# RP2040.net
KiCad netlist of a schematic drawn in Altium Designer
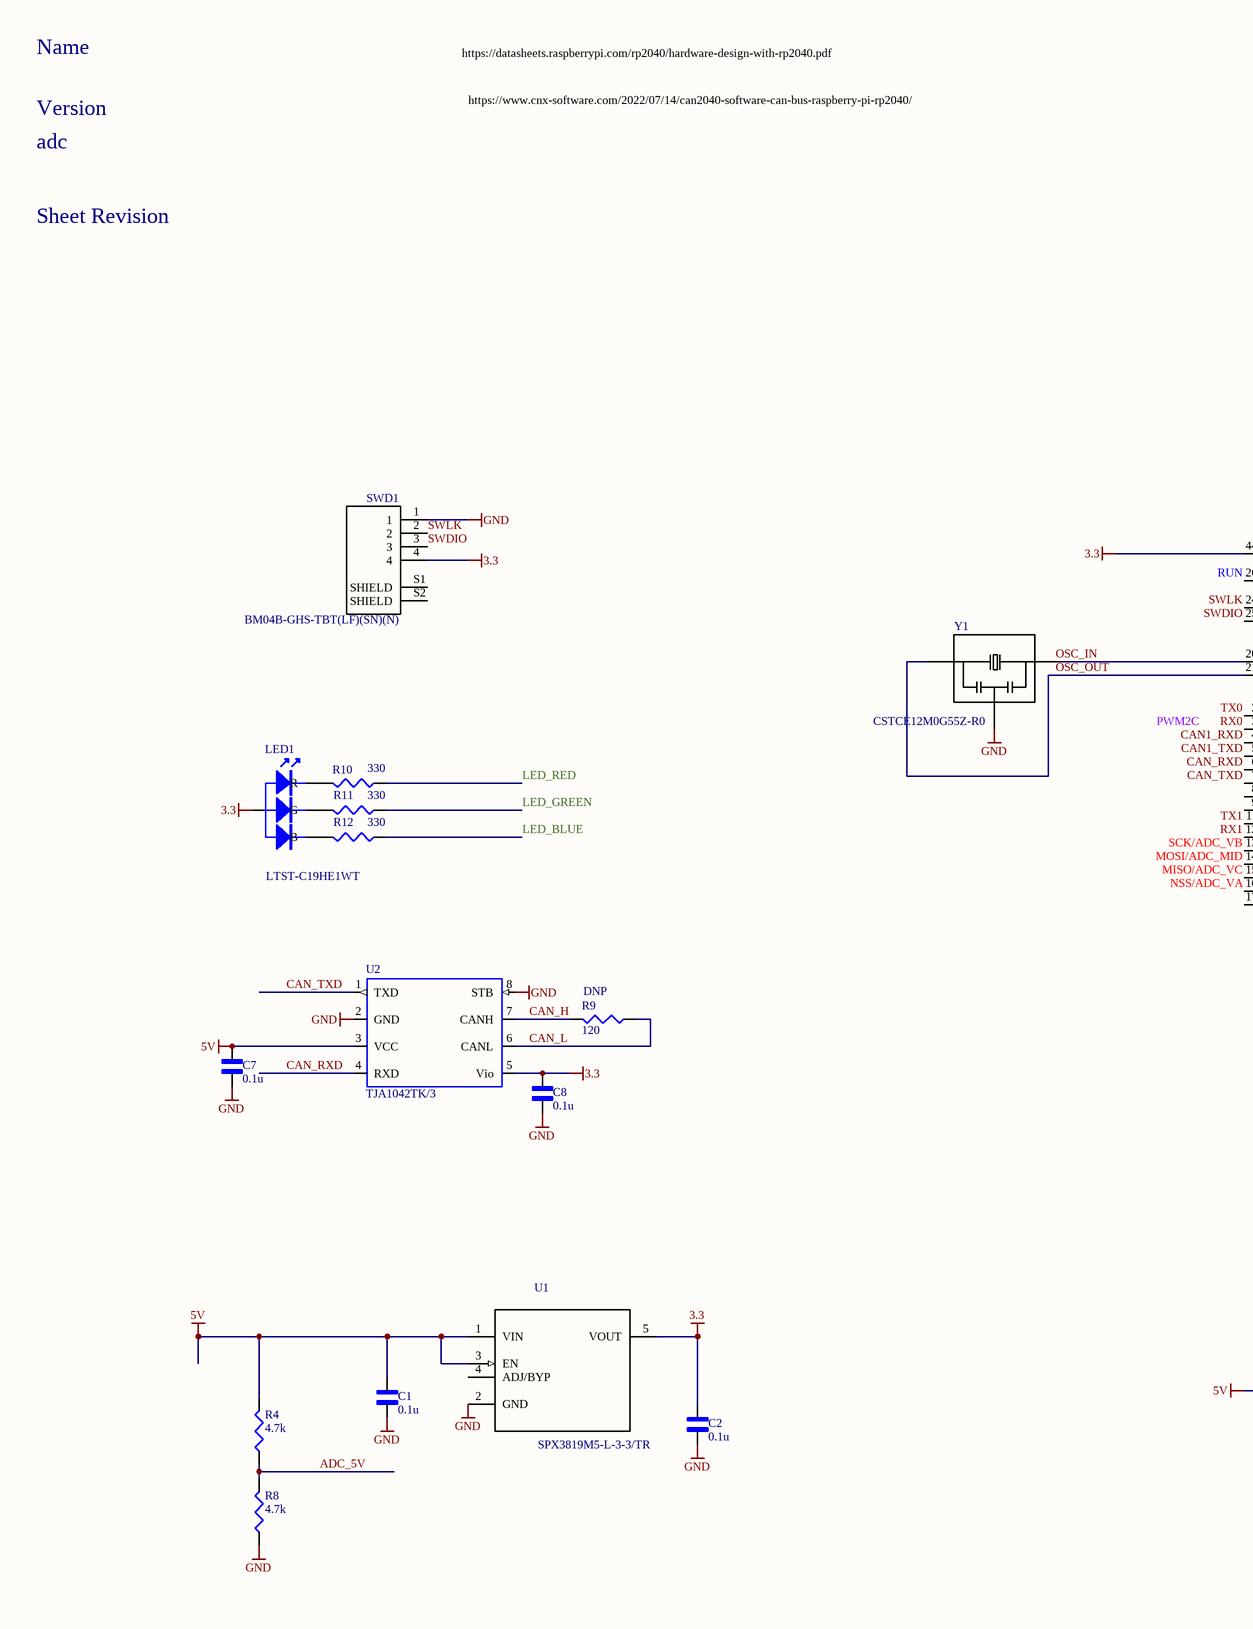
[diagram p0: RP2040.SchDoc, left]
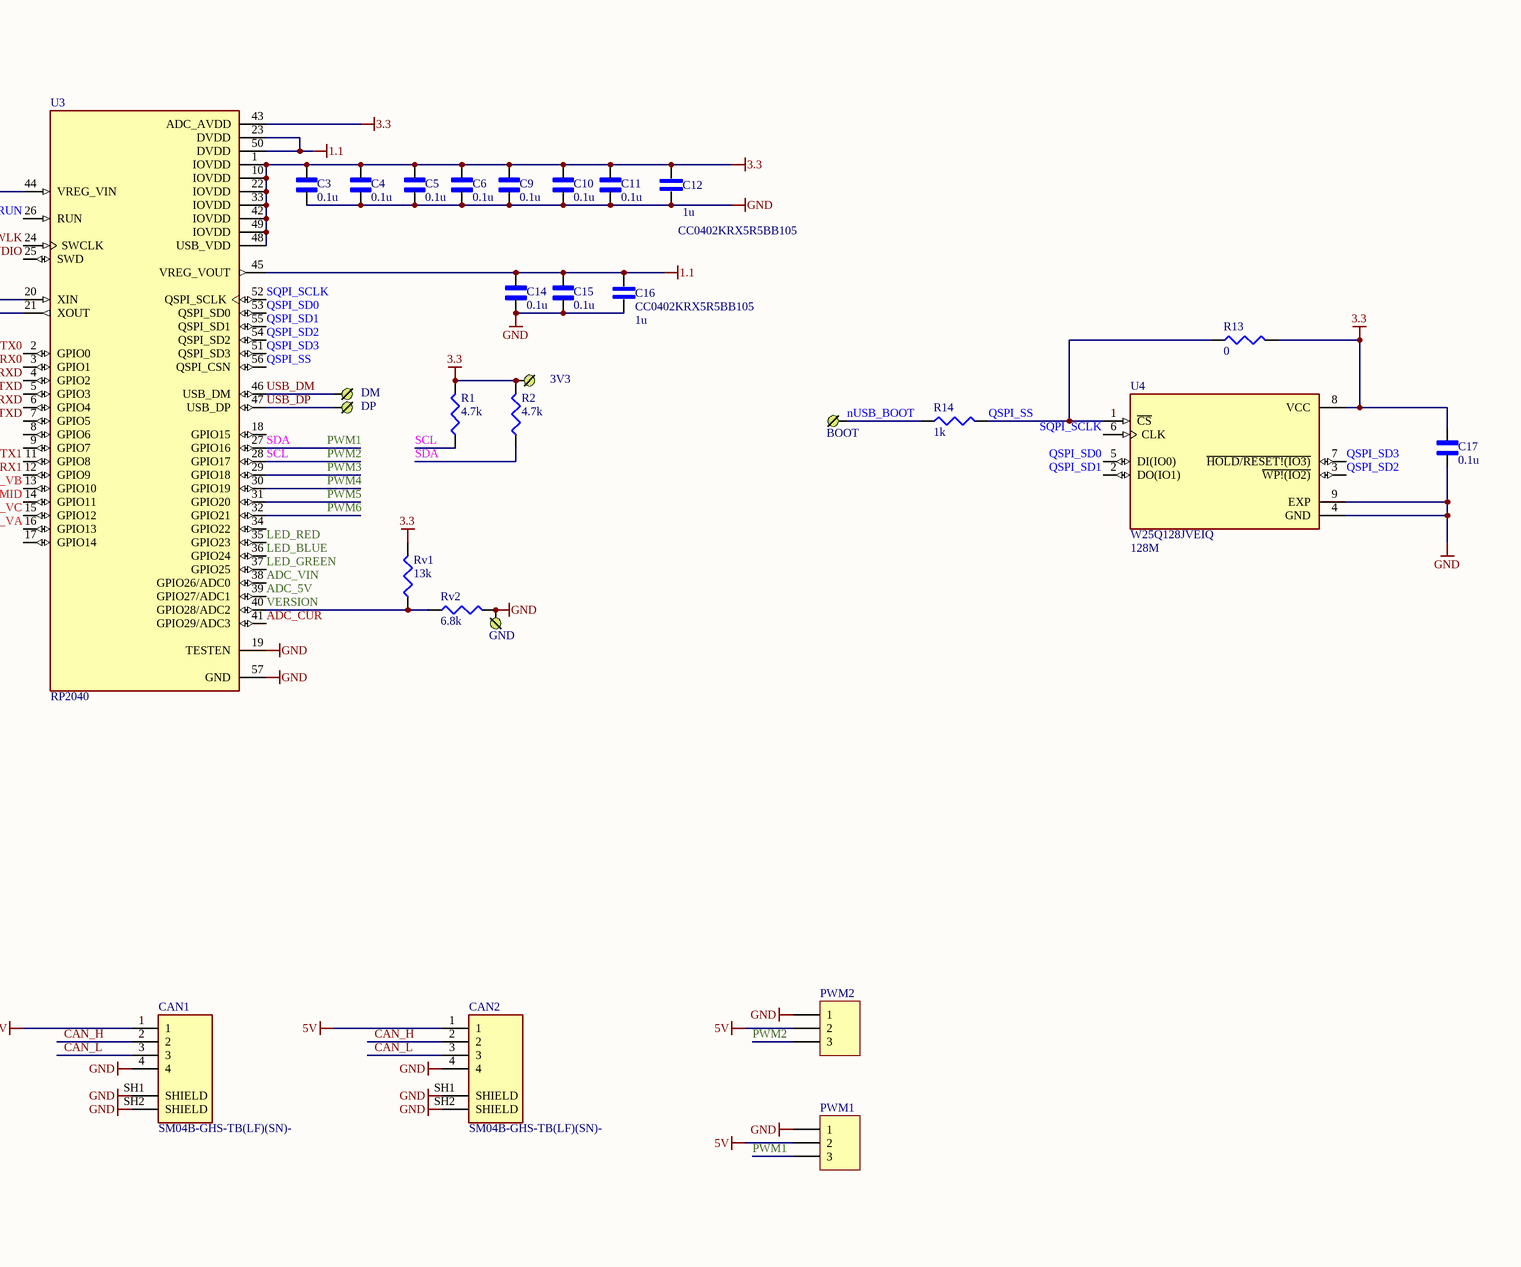
[diagram p1: RP2040.SchDoc, right]

(export (version "E")
  (design (tool "Eeschema 10.0.6"))
  (components
    (comp (ref "3V3") (value "Test Point") (footprint "PAD1") (libsource (lib "lib") (part "PLUG")))
    (comp (ref "BOOT") (value "Test Point") (footprint "PAD1") (libsource (lib "lib") (part "PLUG")))
    (comp (ref "C1")
      (value "0.1u")
      (footprint "CAPC1005X55N")
      (description "GCM155R71H104KE02D, Чип 0402 X7R 0.1uF +10% 50V,Конденсатор")
      (fields (field (name "MF") "Murata") (field (name "MP") "GCM155R71H104KE02D"))
      (libsource (lib "lib") (part "GCM155R71H104KE02D"))
    )
    (comp (ref "C2")
      (value "0.1u")
      (footprint "CAPC1005X55N")
      (description "GCM155R71H104KE02D, Чип 0402 X7R 0.1uF +10% 50V,Конденсатор")
      (fields (field (name "MF") "Murata") (field (name "MP") "GCM155R71H104KE02D"))
      (libsource (lib "lib") (part "GCM155R71H104KE02D"))
    )
    (comp (ref "C3")
      (value "0.1u")
      (footprint "CAPC1005X55N")
      (description "GCM155R71H104KE02D, Чип 0402 X7R 0.1uF +10% 50V,Конденсатор")
      (fields (field (name "MF") "Murata") (field (name "MP") "GCM155R71H104KE02D"))
      (libsource (lib "lib") (part "GCM155R71H104KE02D"))
    )
    (comp (ref "C4")
      (value "0.1u")
      (footprint "CAPC1005X55N")
      (description "GCM155R71H104KE02D, Чип 0402 X7R 0.1uF +10% 50V,Конденсатор")
      (fields (field (name "MF") "Murata") (field (name "MP") "GCM155R71H104KE02D"))
      (libsource (lib "lib") (part "GCM155R71H104KE02D"))
    )
    (comp (ref "C5")
      (value "0.1u")
      (footprint "CAPC1005X55N")
      (description "GCM155R71H104KE02D, Чип 0402 X7R 0.1uF +10% 50V,Конденсатор")
      (fields (field (name "MF") "Murata") (field (name "MP") "GCM155R71H104KE02D"))
      (libsource (lib "lib") (part "GCM155R71H104KE02D"))
    )
    (comp (ref "C6")
      (value "0.1u")
      (footprint "CAPC1005X55N")
      (description "GCM155R71H104KE02D, Чип 0402 X7R 0.1uF +10% 50V,Конденсатор")
      (fields (field (name "MF") "Murata") (field (name "MP") "GCM155R71H104KE02D"))
      (libsource (lib "lib") (part "GCM155R71H104KE02D"))
    )
    (comp (ref "C7")
      (value "0.1u")
      (footprint "CAPC1005X55N")
      (description "GCM155R71H104KE02D, Чип 0402 X7R 0.1uF +10% 50V,Конденсатор")
      (fields (field (name "MF") "Murata") (field (name "MP") "GCM155R71H104KE02D"))
      (libsource (lib "lib") (part "GCM155R71H104KE02D"))
    )
    (comp (ref "C8")
      (value "0.1u")
      (footprint "CAPC1005X55N")
      (description "GCM155R71H104KE02D, Чип 0402 X7R 0.1uF +10% 50V,Конденсатор")
      (fields (field (name "MF") "Murata") (field (name "MP") "GCM155R71H104KE02D"))
      (libsource (lib "lib") (part "GCM155R71H104KE02D"))
    )
    (comp (ref "C9")
      (value "0.1u")
      (footprint "CAPC1005X55N")
      (description "GCM155R71H104KE02D, Чип 0402 X7R 0.1uF +10% 50V,Конденсатор")
      (fields (field (name "MF") "Murata") (field (name "MP") "GCM155R71H104KE02D"))
      (libsource (lib "lib") (part "GCM155R71H104KE02D"))
    )
    (comp (ref "C10")
      (value "0.1u")
      (footprint "CAPC1005X55N")
      (description "GCM155R71H104KE02D, Чип 0402 X7R 0.1uF +10% 50V,Конденсатор")
      (fields (field (name "MF") "Murata") (field (name "MP") "GCM155R71H104KE02D"))
      (libsource (lib "lib") (part "GCM155R71H104KE02D"))
    )
    (comp (ref "C11")
      (value "0.1u")
      (footprint "CAPC1005X55N")
      (description "GCM155R71H104KE02D, Чип 0402 X7R 0.1uF +10% 50V,Конденсатор")
      (fields (field (name "MF") "Murata") (field (name "MP") "GCM155R71H104KE02D"))
      (libsource (lib "lib") (part "GCM155R71H104KE02D"))
    )
    (comp (ref "C12")
      (value "CC0402KRX5R5BB105")
      (footprint "CAPC1005X55N")
      (description "10% 6.3V Ceramic Capacitor X5R 0402 _1005 Metric_")
      (fields (field (name "MF") "Yageo") (field (name "ALTIUM_VALUE") "1u"))
      (libsource (lib "lib") (part "CC0402KRX5R5BB105"))
    )
    (comp (ref "C14")
      (value "0.1u")
      (footprint "CAPC1005X55N")
      (description "GCM155R71H104KE02D, Чип 0402 X7R 0.1uF +10% 50V,Конденсатор")
      (fields (field (name "MF") "Murata") (field (name "MP") "GCM155R71H104KE02D"))
      (libsource (lib "lib") (part "GCM155R71H104KE02D"))
    )
    (comp (ref "C15")
      (value "0.1u")
      (footprint "CAPC1005X55N")
      (description "GCM155R71H104KE02D, Чип 0402 X7R 0.1uF +10% 50V,Конденсатор")
      (fields (field (name "MF") "Murata") (field (name "MP") "GCM155R71H104KE02D"))
      (libsource (lib "lib") (part "GCM155R71H104KE02D"))
    )
    (comp (ref "C16")
      (value "CC0402KRX5R5BB105")
      (footprint "CAPC1005X55N")
      (description "10% 6.3V Ceramic Capacitor X5R 0402 _1005 Metric_")
      (fields (field (name "MF") "Yageo") (field (name "ALTIUM_VALUE") "1u"))
      (libsource (lib "lib") (part "CC0402KRX5R5BB105"))
    )
    (comp (ref "C17")
      (value "0.1u")
      (footprint "CAPC1005X55N")
      (description "GCM155R71H104KE02D, Чип 0402 X7R 0.1uF +10% 50V,Конденсатор")
      (fields (field (name "MF") "Murata") (field (name "MP") "GCM155R71H104KE02D"))
      (libsource (lib "lib") (part "GCM155R71H104KE02D"))
    )
    (comp (ref "CAN1")
      (value "SM04B-GHS-TB(LF)(SN)-")
      (footprint "JST_SM04B-GHS-TB(LF)(SN)-")
      (description "Connector Header Surface Mount, Right Angle 4 position 0.049 _1.25mm_")
      (fields (field (name "MP") "SM04B-GHS-TB(LF)(SN)") (field (name "MF") "JST Sales"))
      (libsource (lib "lib") (part "SM04B-GHS-TB(LF)(SN)-"))
    )
    (comp (ref "CAN2")
      (value "SM04B-GHS-TB(LF)(SN)-")
      (footprint "JST_SM04B-GHS-TB(LF)(SN)-")
      (description "Connector Header Surface Mount, Right Angle 4 position 0.049 _1.25mm_")
      (fields (field (name "MP") "SM04B-GHS-TB(LF)(SN)") (field (name "MF") "JST Sales"))
      (libsource (lib "lib") (part "SM04B-GHS-TB(LF)(SN)-"))
    )
    (comp (ref "DM") (value "Test Point") (footprint "PAD1") (libsource (lib "lib") (part "PLUG")))
    (comp (ref "DP") (value "Test Point") (footprint "PAD1") (libsource (lib "lib") (part "PLUG")))
    (comp (ref "GND") (value "Test Point") (footprint "PAD1") (libsource (lib "lib") (part "PLUG")))
    (comp (ref "LED1")
      (value "LTST-C19HE1WT")
      (footprint "LTST-C19HE1WT")
      (description "Blue/Green/Red")
      (libsource (lib "lib") (part "RGB_LED_5MM"))
    )
    (comp (ref "PWM1")
      (value "A")
      (footprint "HDR Side 3 pin")
      (description "Header, 3-Pin")
      (fields (field (name "MF") "Connfly electronic (Zhenqin)") (field (name "MP") "PLS-3 (DS1021-1x3)"))
      (libsource (lib "DC_DC") (part "Header 3"))
    )
    (comp (ref "PWM2")
      (value "A")
      (footprint "HDR Side 3 pin")
      (description "Header, 3-Pin")
      (fields (field (name "MF") "Connfly electronic (Zhenqin)") (field (name "MP") "PLS-3 (DS1021-1x3)"))
      (libsource (lib "DC_DC") (part "Header 3"))
    )
    (comp (ref "R1")
      (value "4.7k")
      (footprint "RESC1005X40N")
      (description "0.062Вт 0402 4.7 кОм, 1%, Чип резистор (SMD)")
      (fields (field (name "MF") "Yageo or NXP") (field (name "MP") "RC0402FR-074K7L"))
      (libsource (lib "lib") (part "RC0402FR-074K7L"))
    )
    (comp (ref "R2")
      (value "4.7k")
      (footprint "RESC1005X40N")
      (description "0.062Вт 0402 4.7 кОм, 1%, Чип резистор (SMD)")
      (fields (field (name "MF") "Yageo or NXP") (field (name "MP") "RC0402FR-074K7L"))
      (libsource (lib "lib") (part "RC0402FR-074K7L"))
    )
    (comp (ref "R4")
      (value "4.7k")
      (footprint "RESC1005X40N")
      (description "0.062Вт 0402 4.7 кОм, 1%, Чип резистор (SMD)")
      (fields (field (name "MF") "Yageo or NXP") (field (name "MP") "RC0402FR-074K7L"))
      (libsource (lib "lib") (part "RC0402FR-074K7L"))
    )
    (comp (ref "R8")
      (value "4.7k")
      (footprint "RESC1005X40N")
      (description "0.062Вт 0402 4.7 кОм, 1%, Чип резистор (SMD)")
      (fields (field (name "MF") "Yageo or NXP") (field (name "MP") "RC0402FR-074K7L"))
      (libsource (lib "lib") (part "RC0402FR-074K7L"))
    )
    (comp (ref "R9")
      (value "120")
      (footprint "J1-0603")
      (description "120 Ohms 1 0.1 W 1 10 W Chip Resistor 0603 1608 Metric Thick Film")
      (fields
        (field (name "INSTRUCTIONS") "DNP")
        (field (name "MP") "RC0603FR-07120RL")
        (field (name "Comment") "Res3")
      )
      (libsource (lib "Miscellaneous Devices") (part "Res3"))
    )
    (comp (ref "R10")
      (value "330")
      (footprint "RESC1005X40N")
      (description "0.062Вт 0402 330 Ом, 1%, Чип резистор (SMD)")
      (fields (field (name "MF") "Yageo or NXP") (field (name "MP") "RC0402FR-07330RL"))
      (libsource (lib "lib") (part "RC0402FR-07330RL"))
    )
    (comp (ref "R11")
      (value "330")
      (footprint "RESC1005X40N")
      (description "0.062Вт 0402 330 Ом, 1%, Чип резистор (SMD)")
      (fields (field (name "MF") "Yageo or NXP") (field (name "MP") "RC0402FR-07330RL"))
      (libsource (lib "lib") (part "RC0402FR-07330RL"))
    )
    (comp (ref "R12")
      (value "330")
      (footprint "RESC1005X40N")
      (description "0.062Вт 0402 330 Ом, 1%, Чип резистор (SMD)")
      (fields (field (name "MF") "Yageo or NXP") (field (name "MP") "RC0402FR-07330RL"))
      (libsource (lib "lib") (part "RC0402FR-07330RL"))
    )
    (comp (ref "R13")
      (value "0")
      (footprint "J1-0603")
      (description "0 Ohms ±1% 0.1W, 1/10W Chip Resistor 0603 (1608 Metric) Moisture Resistant Thick Film")
      (fields (field (name "MF") "Yageo or NXP") (field (name "MP") "RC0603FR-070RL"))
      (libsource (lib "lib") (part "RC0603FR-070RL"))
    )
    (comp (ref "R14")
      (value "1k")
      (footprint "RESC1005X40N")
      (description "0.062Вт 0402 1 кОм, 1%, Чип резистор (SMD)")
      (fields (field (name "MF") "Yageo or NXP") (field (name "MP") "RC0402FR-071KL"))
      (libsource (lib "lib") (part "RC0402FR-071KL"))
    )
    (comp (ref "Rv1")
      (value "13k")
      (footprint "RESC1005X40N")
      (description "0.062Вт 0402 13 кОм, 1%, Чип резистор (SMD)")
      (fields (field (name "MF") "Yageo or NXP") (field (name "MP") "RC0402FR-0713KL"))
      (libsource (lib "lib") (part "RC0402FR-0713KL"))
    )
    (comp (ref "Rv2")
      (value "6.8k")
      (footprint "RESC1005X40N")
      (description "0.062Вт 0402 6.8 кОм, 1%, Чип резистор (SMD)")
      (fields (field (name "MF") "Yageo or NXP") (field (name "MP") "RC0402FR-076K8L"))
      (libsource (lib "lib") (part "RC0402FR-076K8L"))
    )
    (comp (ref "SWD1")
      (value "BM04B-GHS-TBT(LF)(SN)(N)")
      (footprint "JST_BM04B-GHS-holes")
      (description "Conn Shrouded Header HDR 4 POS 1.25mm Solder ST SMD Reel")
      (fields (field (name "MF") "JST Sales") (field (name "MP") "SM04B-GHS-TB(LF)(SN)"))
      (libsource (lib "lib") (part "BM04B-GHS-TBT(LF)(SN)(N)"))
    )
    (comp (ref "U1")
      (value "SPX3819M5-L-3-3/TR")
      (footprint "*SOT95P280X145-5N")
      (description "Low Dropout Voltage Regulator, Adjustable 0.5A, В±1%, 2.5 to 16 Vin, 5-Pin SOT-23")
      (fields (field (name "MF") "MaxLinear, Inc."))
      (libsource (lib "DC_DC") (part "SPX3819M5-L"))
    )
    (comp (ref "U2")
      (value "TJA1042TK/3")
      (footprint "SOT782-1")
      (description "1/1 Transceiver Half CANbus 8-SO")
      (fields (field (name "MF") "NXP USA"))
      (libsource (lib "lib") (part "TJA1042TK/3"))
    )
    (comp (ref "U3")
      (value "RP2040")
      (footprint "QFN40P700X700X90-57N")
      (libsource (lib "lib") (part "RP2040"))
    )
    (comp (ref "U4")
      (value "W25Q128JVEIQ")
      (footprint "SON127P500X600X80-9N")
      (description "FLASH - NOR Memory IC 128Mb (16M x 8) SPI - Quad I/O, QPI, DTR 133 MHz 8-SOIC")
      (fields
        (field (name "MF") "Winbond Electronics")
        (field (name "MP") "W25Q128JVSIQ")
        (field (name "ALTIUM_VALUE") "128M")
      )
      (libsource (lib "lib") (part "W25Q128JVEIQ"))
    )
    (comp (ref "Y1")
      (value "CSTCE12M0G55Z-R0")
      (footprint "*OSC_CSTCE8M00G55-R0")
      (description "Ceramic Resonator, 12 MHz, +/- 0.5%, -40 to 125 degC, 3-Pin SMD, RoHS, Tape and Reel")
      (fields (field (name "MF") "Murata"))
      (libsource (lib "lib") (part "CSTCE12M0G55Z-R0"))
    )
  )
  (nets
    (net (code "1") (name "/ADC_5V") (class "Default")
      (node (ref "R4") (pin "1") (pinfunction "1_1") (pintype "passive"))
      (node (ref "R8") (pin "2") (pinfunction "2_2") (pintype "passive"))
      (node (ref "U3") (pin "39") (pinfunction "GPIO27/ADC1_39") (pintype "bidirectional"))
    )
    (net (code "2") (name "/ADC_CUR") (class "Default")
      (node (ref "U3") (pin "41") (pinfunction "GPIO29/ADC3_41") (pintype "bidirectional"))
    )
    (net (code "3") (name "/ADC_VIN") (class "Default")
      (node (ref "U3") (pin "38") (pinfunction "GPIO26/ADC0_38") (pintype "bidirectional"))
    )
    (net (code "4") (name "/CAN1_RXD") (class "Default")
      (node (ref "U3") (pin "4") (pinfunction "GPIO2_4") (pintype "bidirectional"))
    )
    (net (code "5") (name "/CAN1_TXD") (class "Default")
      (node (ref "U3") (pin "5") (pinfunction "GPIO3_5") (pintype "bidirectional"))
    )
    (net (code "6") (name "/CAN_H") (class "Default")
      (node (ref "CAN1") (pin "2") (pinfunction "2_2") (pintype "passive"))
      (node (ref "CAN2") (pin "2") (pinfunction "2_2") (pintype "passive"))
      (node (ref "R9") (pin "2") (pinfunction "2_2") (pintype "passive"))
      (node (ref "U2") (pin "7") (pinfunction "CANH_7") (pintype "bidirectional"))
    )
    (net (code "7") (name "/CAN_L") (class "Default")
      (node (ref "CAN1") (pin "3") (pinfunction "3_3") (pintype "passive"))
      (node (ref "CAN2") (pin "3") (pinfunction "3_3") (pintype "passive"))
      (node (ref "R9") (pin "1") (pinfunction "1_1") (pintype "passive"))
      (node (ref "U2") (pin "6") (pinfunction "CANL_6") (pintype "bidirectional"))
    )
    (net (code "8") (name "/CAN_RXD") (class "Default")
      (node (ref "U2") (pin "4") (pinfunction "RXD_4") (pintype "bidirectional"))
      (node (ref "U3") (pin "6") (pinfunction "GPIO4_6") (pintype "bidirectional"))
    )
    (net (code "9") (name "/CAN_TXD") (class "Default")
      (node (ref "U2") (pin "1") (pinfunction "TXD_1") (pintype "output"))
      (node (ref "U3") (pin "7") (pinfunction "GPIO5_7") (pintype "bidirectional"))
    )
    (net (code "10") (name "/LED_BLUE") (class "Default")
      (node (ref "R12") (pin "1") (pinfunction "1_1") (pintype "passive"))
      (node (ref "U3") (pin "36") (pinfunction "GPIO24_36") (pintype "bidirectional"))
    )
    (net (code "11") (name "/LED_GREEN") (class "Default")
      (node (ref "R11") (pin "1") (pinfunction "1_1") (pintype "passive"))
      (node (ref "U3") (pin "37") (pinfunction "GPIO25_37") (pintype "bidirectional"))
    )
    (net (code "12") (name "/LED_RED") (class "Default")
      (node (ref "R10") (pin "1") (pinfunction "1_1") (pintype "passive"))
      (node (ref "U3") (pin "35") (pinfunction "GPIO23_35") (pintype "bidirectional"))
    )
    (net (code "13") (name "/MISO{slash}ADC_VC") (class "Default")
      (node (ref "U3") (pin "15") (pinfunction "GPIO12_15") (pintype "bidirectional"))
    )
    (net (code "14") (name "/MOSI{slash}ADC_MID") (class "Default")
      (node (ref "U3") (pin "14") (pinfunction "GPIO11_14") (pintype "bidirectional"))
    )
    (net (code "15") (name "/NSS{slash}ADC_VA") (class "Default")
      (node (ref "U3") (pin "16") (pinfunction "GPIO13_16") (pintype "bidirectional"))
    )
    (net (code "17") (name "/OSC_OUT") (class "Default")
      (node (ref "U3") (pin "21") (pinfunction "XOUT_21") (pintype "output"))
      (node (ref "Y1") (pin "1") (pinfunction "1_1") (pintype "passive"))
    )
    (net (code "18") (name "/PWM1") (class "Default")
      (node (ref "PWM1") (pin "3") (pinfunction "3_3") (pintype "passive"))
      (node (ref "R2") (pin "1") (pinfunction "1_1") (pintype "passive"))
      (node (ref "U3") (pin "27") (pinfunction "GPIO16_27") (pintype "bidirectional"))
    )
    (net (code "19") (name "/PWM2") (class "Default")
      (node (ref "PWM2") (pin "3") (pinfunction "3_3") (pintype "passive"))
      (node (ref "R1") (pin "1") (pinfunction "1_1") (pintype "passive"))
      (node (ref "U3") (pin "28") (pinfunction "GPIO17_28") (pintype "bidirectional"))
    )
    (net (code "21") (name "/PWM3") (class "Default")
      (node (ref "U3") (pin "29") (pinfunction "GPIO18_29") (pintype "bidirectional"))
    )
    (net (code "22") (name "/PWM4") (class "Default")
      (node (ref "U3") (pin "30") (pinfunction "GPIO19_30") (pintype "bidirectional"))
    )
    (net (code "23") (name "/PWM5") (class "Default")
      (node (ref "U3") (pin "31") (pinfunction "GPIO20_31") (pintype "bidirectional"))
    )
    (net (code "24") (name "/PWM6") (class "Default")
      (node (ref "U3") (pin "32") (pinfunction "GPIO21_32") (pintype "bidirectional"))
    )
    (net (code "25") (name "/QSPI_SD0") (class "Default")
      (node (ref "U3") (pin "53") (pinfunction "QSPI_SD0_53") (pintype "bidirectional"))
      (node (ref "U4") (pin "5") (pinfunction "DI(IO0)_5") (pintype "bidirectional"))
    )
    (net (code "26") (name "/QSPI_SD1") (class "Default")
      (node (ref "U3") (pin "55") (pinfunction "QSPI_SD1_55") (pintype "bidirectional"))
      (node (ref "U4") (pin "2") (pinfunction "DO(IO1)_2") (pintype "bidirectional"))
    )
    (net (code "27") (name "/QSPI_SD2") (class "Default")
      (node (ref "U3") (pin "54") (pinfunction "QSPI_SD2_54") (pintype "bidirectional"))
      (node (ref "U4") (pin "3") (pinfunction "~{WP!(IO2)}_3") (pintype "bidirectional"))
    )
    (net (code "28") (name "/QSPI_SD3") (class "Default")
      (node (ref "U3") (pin "51") (pinfunction "QSPI_SD3_51") (pintype "bidirectional"))
      (node (ref "U4") (pin "7") (pinfunction "~{HOLD/RESET!(IO3)}_7") (pintype "bidirectional"))
    )
    (net (code "29") (name "/QSPI_SS") (class "Default")
      (node (ref "R13") (pin "1") (pinfunction "1_1") (pintype "passive"))
      (node (ref "R14") (pin "2") (pinfunction "2_2") (pintype "passive"))
      (node (ref "U3") (pin "56") (pinfunction "QSPI_CSN_56") (pintype "bidirectional"))
      (node (ref "U4") (pin "1") (pinfunction "~{CS}_1") (pintype "input"))
    )
    (net (code "30") (name "/RUN") (class "Default")
      (node (ref "U3") (pin "26") (pinfunction "RUN_26") (pintype "input"))
    )
    (net (code "31") (name "/RX0") (class "Default")
      (node (ref "U3") (pin "3") (pinfunction "GPIO1_3") (pintype "bidirectional"))
    )
    (net (code "32") (name "/RX1") (class "Default")
      (node (ref "U3") (pin "12") (pinfunction "GPIO9_12") (pintype "bidirectional"))
    )
    (net (code "33") (name "/SCK{slash}ADC_VB") (class "Default")
      (node (ref "U3") (pin "13") (pinfunction "GPIO10_13") (pintype "bidirectional"))
    )
    (net (code "34") (name "/SQPI_SCLK") (class "Default")
      (node (ref "U3") (pin "52") (pinfunction "QSPI_SCLK_52") (pintype "bidirectional"))
      (node (ref "U4") (pin "6") (pinfunction "CLK_6") (pintype "input"))
    )
    (net (code "35") (name "/SWDIO") (class "Default")
      (node (ref "SWD1") (pin "3") (pinfunction "3_3") (pintype "passive"))
      (node (ref "U3") (pin "25") (pinfunction "SWD_25") (pintype "bidirectional"))
    )
    (net (code "36") (name "/SWLK") (class "Default")
      (node (ref "SWD1") (pin "2") (pinfunction "2_2") (pintype "passive"))
      (node (ref "U3") (pin "24") (pinfunction "SWCLK_24") (pintype "input"))
    )
    (net (code "37") (name "/TX0") (class "Default")
      (node (ref "U3") (pin "2") (pinfunction "GPIO0_2") (pintype "bidirectional"))
    )
    (net (code "38") (name "/TX1") (class "Default")
      (node (ref "U3") (pin "11") (pinfunction "GPIO8_11") (pintype "bidirectional"))
    )
    (net (code "39") (name "/USB_DM") (class "Default")
      (node (ref "DM") (pin "1") (pintype "passive"))
      (node (ref "U3") (pin "46") (pinfunction "USB_DM_46") (pintype "bidirectional"))
    )
    (net (code "40") (name "/USB_DP") (class "Default")
      (node (ref "DP") (pin "1") (pintype "passive"))
      (node (ref "U3") (pin "47") (pinfunction "USB_DP_47") (pintype "bidirectional"))
    )
    (net (code "41") (name "/VERSION") (class "Default")
      (node (ref "Rv1") (pin "1") (pinfunction "1_1") (pintype "passive"))
      (node (ref "Rv2") (pin "1") (pinfunction "1_1") (pintype "passive"))
      (node (ref "U3") (pin "40") (pinfunction "GPIO28/ADC2_40") (pintype "bidirectional"))
    )
    (net (code "42") (name "/nUSB_BOOT") (class "Default")
      (node (ref "BOOT") (pin "1") (pintype "passive"))
      (node (ref "R14") (pin "1") (pinfunction "1_1") (pintype "passive"))
    )
    (net (code "43") (name "1.1") (class "Default")
      (node (ref "C14") (pin "2") (pinfunction "2_2") (pintype "passive"))
      (node (ref "C15") (pin "2") (pinfunction "2_2") (pintype "passive"))
      (node (ref "C16") (pin "1") (pinfunction "1_1") (pintype "passive"))
      (node (ref "U3") (pin "23") (pinfunction "DVDD_23") (pintype "power_in"))
      (node (ref "U3") (pin "45") (pinfunction "VREG_VOUT_45") (pintype "output"))
      (node (ref "U3") (pin "50") (pinfunction "DVDD_50") (pintype "power_in"))
    )
    (net (code "44") (name "3.3") (class "Default")
      (node (ref "3V3") (pin "1") (pintype "passive"))
      (node (ref "C10") (pin "2") (pinfunction "2_2") (pintype "passive"))
      (node (ref "C11") (pin "2") (pinfunction "2_2") (pintype "passive"))
      (node (ref "C12") (pin "1") (pinfunction "1_1") (pintype "passive"))
      (node (ref "C17") (pin "2") (pinfunction "2_2") (pintype "passive"))
      (node (ref "C2") (pin "2") (pinfunction "2_2") (pintype "passive"))
      (node (ref "C3") (pin "2") (pinfunction "2_2") (pintype "passive"))
      (node (ref "C4") (pin "2") (pinfunction "2_2") (pintype "passive"))
      (node (ref "C5") (pin "2") (pinfunction "2_2") (pintype "passive"))
      (node (ref "C6") (pin "2") (pinfunction "2_2") (pintype "passive"))
      (node (ref "C8") (pin "2") (pinfunction "2_2") (pintype "passive"))
      (node (ref "C9") (pin "2") (pinfunction "2_2") (pintype "passive"))
      (node (ref "LED1") (pin "4") (pinfunction "A_4") (pintype "passive"))
      (node (ref "R1") (pin "2") (pinfunction "2_2") (pintype "passive"))
      (node (ref "R13") (pin "2") (pinfunction "2_2") (pintype "passive"))
      (node (ref "R2") (pin "2") (pinfunction "2_2") (pintype "passive"))
      (node (ref "Rv1") (pin "2") (pinfunction "2_2") (pintype "passive"))
      (node (ref "SWD1") (pin "4") (pinfunction "4_4") (pintype "passive"))
      (node (ref "U1") (pin "5") (pinfunction "VOUT_5") (pintype "power_in"))
      (node (ref "U2") (pin "5") (pinfunction "Vio_5") (pintype "power_in"))
      (node (ref "U3") (pin "1") (pinfunction "IOVDD_1") (pintype "power_in"))
      (node (ref "U3") (pin "10") (pinfunction "IOVDD_10") (pintype "power_in"))
      (node (ref "U3") (pin "22") (pinfunction "IOVDD_22") (pintype "power_in"))
      (node (ref "U3") (pin "33") (pinfunction "IOVDD_33") (pintype "power_in"))
      (node (ref "U3") (pin "42") (pinfunction "IOVDD_42") (pintype "power_in"))
      (node (ref "U3") (pin "43") (pinfunction "ADC_AVDD_43") (pintype "power_in"))
      (node (ref "U3") (pin "44") (pinfunction "VREG_VIN_44") (pintype "input"))
      (node (ref "U3") (pin "48") (pinfunction "USB_VDD_48") (pintype "power_in"))
      (node (ref "U3") (pin "49") (pinfunction "IOVDD_49") (pintype "power_in"))
      (node (ref "U4") (pin "8") (pinfunction "VCC_8") (pintype "power_in"))
    )
    (net (code "45") (name "5V") (class "Default")
      (node (ref "C1") (pin "2") (pinfunction "2_2") (pintype "passive"))
      (node (ref "C7") (pin "2") (pinfunction "2_2") (pintype "passive"))
      (node (ref "CAN1") (pin "1") (pinfunction "1_1") (pintype "passive"))
      (node (ref "CAN2") (pin "1") (pinfunction "1_1") (pintype "passive"))
      (node (ref "PWM1") (pin "2") (pinfunction "2_2") (pintype "passive"))
      (node (ref "PWM2") (pin "2") (pinfunction "2_2") (pintype "passive"))
      (node (ref "R4") (pin "2") (pinfunction "2_2") (pintype "passive"))
      (node (ref "U1") (pin "1") (pinfunction "VIN_1") (pintype "power_in"))
      (node (ref "U1") (pin "3") (pinfunction "EN_3") (pintype "input"))
      (node (ref "U2") (pin "3") (pinfunction "VCC_3") (pintype "power_in"))
    )
    (net (code "46") (name "GND") (class "Default")
      (node (ref "C1") (pin "1") (pinfunction "1_1") (pintype "passive"))
      (node (ref "C10") (pin "1") (pinfunction "1_1") (pintype "passive"))
      (node (ref "C11") (pin "1") (pinfunction "1_1") (pintype "passive"))
      (node (ref "C12") (pin "2") (pinfunction "2_2") (pintype "passive"))
      (node (ref "C14") (pin "1") (pinfunction "1_1") (pintype "passive"))
      (node (ref "C15") (pin "1") (pinfunction "1_1") (pintype "passive"))
      (node (ref "C16") (pin "2") (pinfunction "2_2") (pintype "passive"))
      (node (ref "C17") (pin "1") (pinfunction "1_1") (pintype "passive"))
      (node (ref "C2") (pin "1") (pinfunction "1_1") (pintype "passive"))
      (node (ref "C3") (pin "1") (pinfunction "1_1") (pintype "passive"))
      (node (ref "C4") (pin "1") (pinfunction "1_1") (pintype "passive"))
      (node (ref "C5") (pin "1") (pinfunction "1_1") (pintype "passive"))
      (node (ref "C6") (pin "1") (pinfunction "1_1") (pintype "passive"))
      (node (ref "C7") (pin "1") (pinfunction "1_1") (pintype "passive"))
      (node (ref "C8") (pin "1") (pinfunction "1_1") (pintype "passive"))
      (node (ref "C9") (pin "1") (pinfunction "1_1") (pintype "passive"))
      (node (ref "CAN1") (pin "4") (pinfunction "4_4") (pintype "passive"))
      (node (ref "CAN1") (pin "SH1") (pinfunction "SHIELD_SH1") (pintype "power_in"))
      (node (ref "CAN1") (pin "SH2") (pinfunction "SHIELD_SH2") (pintype "power_in"))
      (node (ref "CAN2") (pin "4") (pinfunction "4_4") (pintype "passive"))
      (node (ref "CAN2") (pin "SH1") (pinfunction "SHIELD_SH1") (pintype "power_in"))
      (node (ref "CAN2") (pin "SH2") (pinfunction "SHIELD_SH2") (pintype "power_in"))
      (node (ref "GND") (pin "1") (pintype "passive"))
      (node (ref "PWM1") (pin "1") (pinfunction "1_1") (pintype "passive"))
      (node (ref "PWM2") (pin "1") (pinfunction "1_1") (pintype "passive"))
      (node (ref "R8") (pin "1") (pinfunction "1_1") (pintype "passive"))
      (node (ref "Rv2") (pin "2") (pinfunction "2_2") (pintype "passive"))
      (node (ref "SWD1") (pin "1") (pinfunction "1_1") (pintype "passive"))
      (node (ref "U1") (pin "2") (pinfunction "GND_2") (pintype "passive"))
      (node (ref "U2") (pin "2") (pinfunction "GND_2") (pintype "power_in"))
      (node (ref "U2") (pin "8") (pinfunction "STB_8") (pintype "input"))
      (node (ref "U3") (pin "19") (pinfunction "TESTEN_19") (pintype "passive"))
      (node (ref "U3") (pin "57") (pinfunction "GND_57") (pintype "power_in"))
      (node (ref "U4") (pin "4") (pinfunction "GND_4") (pintype "power_in"))
      (node (ref "U4") (pin "9") (pinfunction "EXP_9") (pintype "passive"))
      (node (ref "Y1") (pin "2") (pinfunction "2_2") (pintype "power_in"))
    )
    (net (code "47") (name "Net-(LED1-B)") (class "Default")
      (node (ref "LED1") (pin "3") (pinfunction "B_3") (pintype "passive"))
      (node (ref "R12") (pin "2") (pinfunction "2_2") (pintype "passive"))
    )
    (net (code "48") (name "Net-(LED1-G)") (class "Default")
      (node (ref "LED1") (pin "2") (pinfunction "G_2") (pintype "passive"))
      (node (ref "R11") (pin "2") (pinfunction "2_2") (pintype "passive"))
    )
    (net (code "49") (name "Net-(LED1-R)") (class "Default")
      (node (ref "LED1") (pin "1") (pinfunction "R_1") (pintype "passive"))
      (node (ref "R10") (pin "2") (pinfunction "2_2") (pintype "passive"))
    )
    (net (code "50") (name "Net-(U3-XIN)") (class "Default")
      (node (ref "U3") (pin "20") (pinfunction "XIN_20") (pintype "input"))
      (node (ref "Y1") (pin "3") (pinfunction "3_3") (pintype "passive"))
    )
    (net (code "51") (name "unconnected-(SWD1-SHIELD-PadS1)") (class "Default")
      (node (ref "SWD1") (pin "S1") (pinfunction "SHIELD_S1") (pintype "passive"))
    )
    (net (code "52") (name "unconnected-(SWD1-SHIELD-PadS2)") (class "Default")
      (node (ref "SWD1") (pin "S2") (pinfunction "SHIELD_S2") (pintype "passive"))
    )
    (net (code "53") (name "unconnected-(U1-ADJ{slash}BYP-Pad4)") (class "Default")
      (node (ref "U1") (pin "4") (pinfunction "ADJ/BYP_4") (pintype "passive"))
    )
    (net (code "54") (name "unconnected-(U3-GPIO6-Pad8)") (class "Default")
      (node (ref "U3") (pin "8") (pinfunction "GPIO6_8") (pintype "bidirectional"))
    )
    (net (code "55") (name "unconnected-(U3-GPIO7-Pad9)") (class "Default")
      (node (ref "U3") (pin "9") (pinfunction "GPIO7_9") (pintype "bidirectional"))
    )
    (net (code "56") (name "unconnected-(U3-GPIO14-Pad17)") (class "Default")
      (node (ref "U3") (pin "17") (pinfunction "GPIO14_17") (pintype "bidirectional"))
    )
    (net (code "57") (name "unconnected-(U3-GPIO15-Pad18)") (class "Default")
      (node (ref "U3") (pin "18") (pinfunction "GPIO15_18") (pintype "bidirectional"))
    )
    (net (code "58") (name "unconnected-(U3-GPIO22-Pad34)") (class "Default")
      (node (ref "U3") (pin "34") (pinfunction "GPIO22_34") (pintype "bidirectional"))
    )
  )
)
